# Memory.net
KiCad netlist of a schematic drawn in Altium Designer
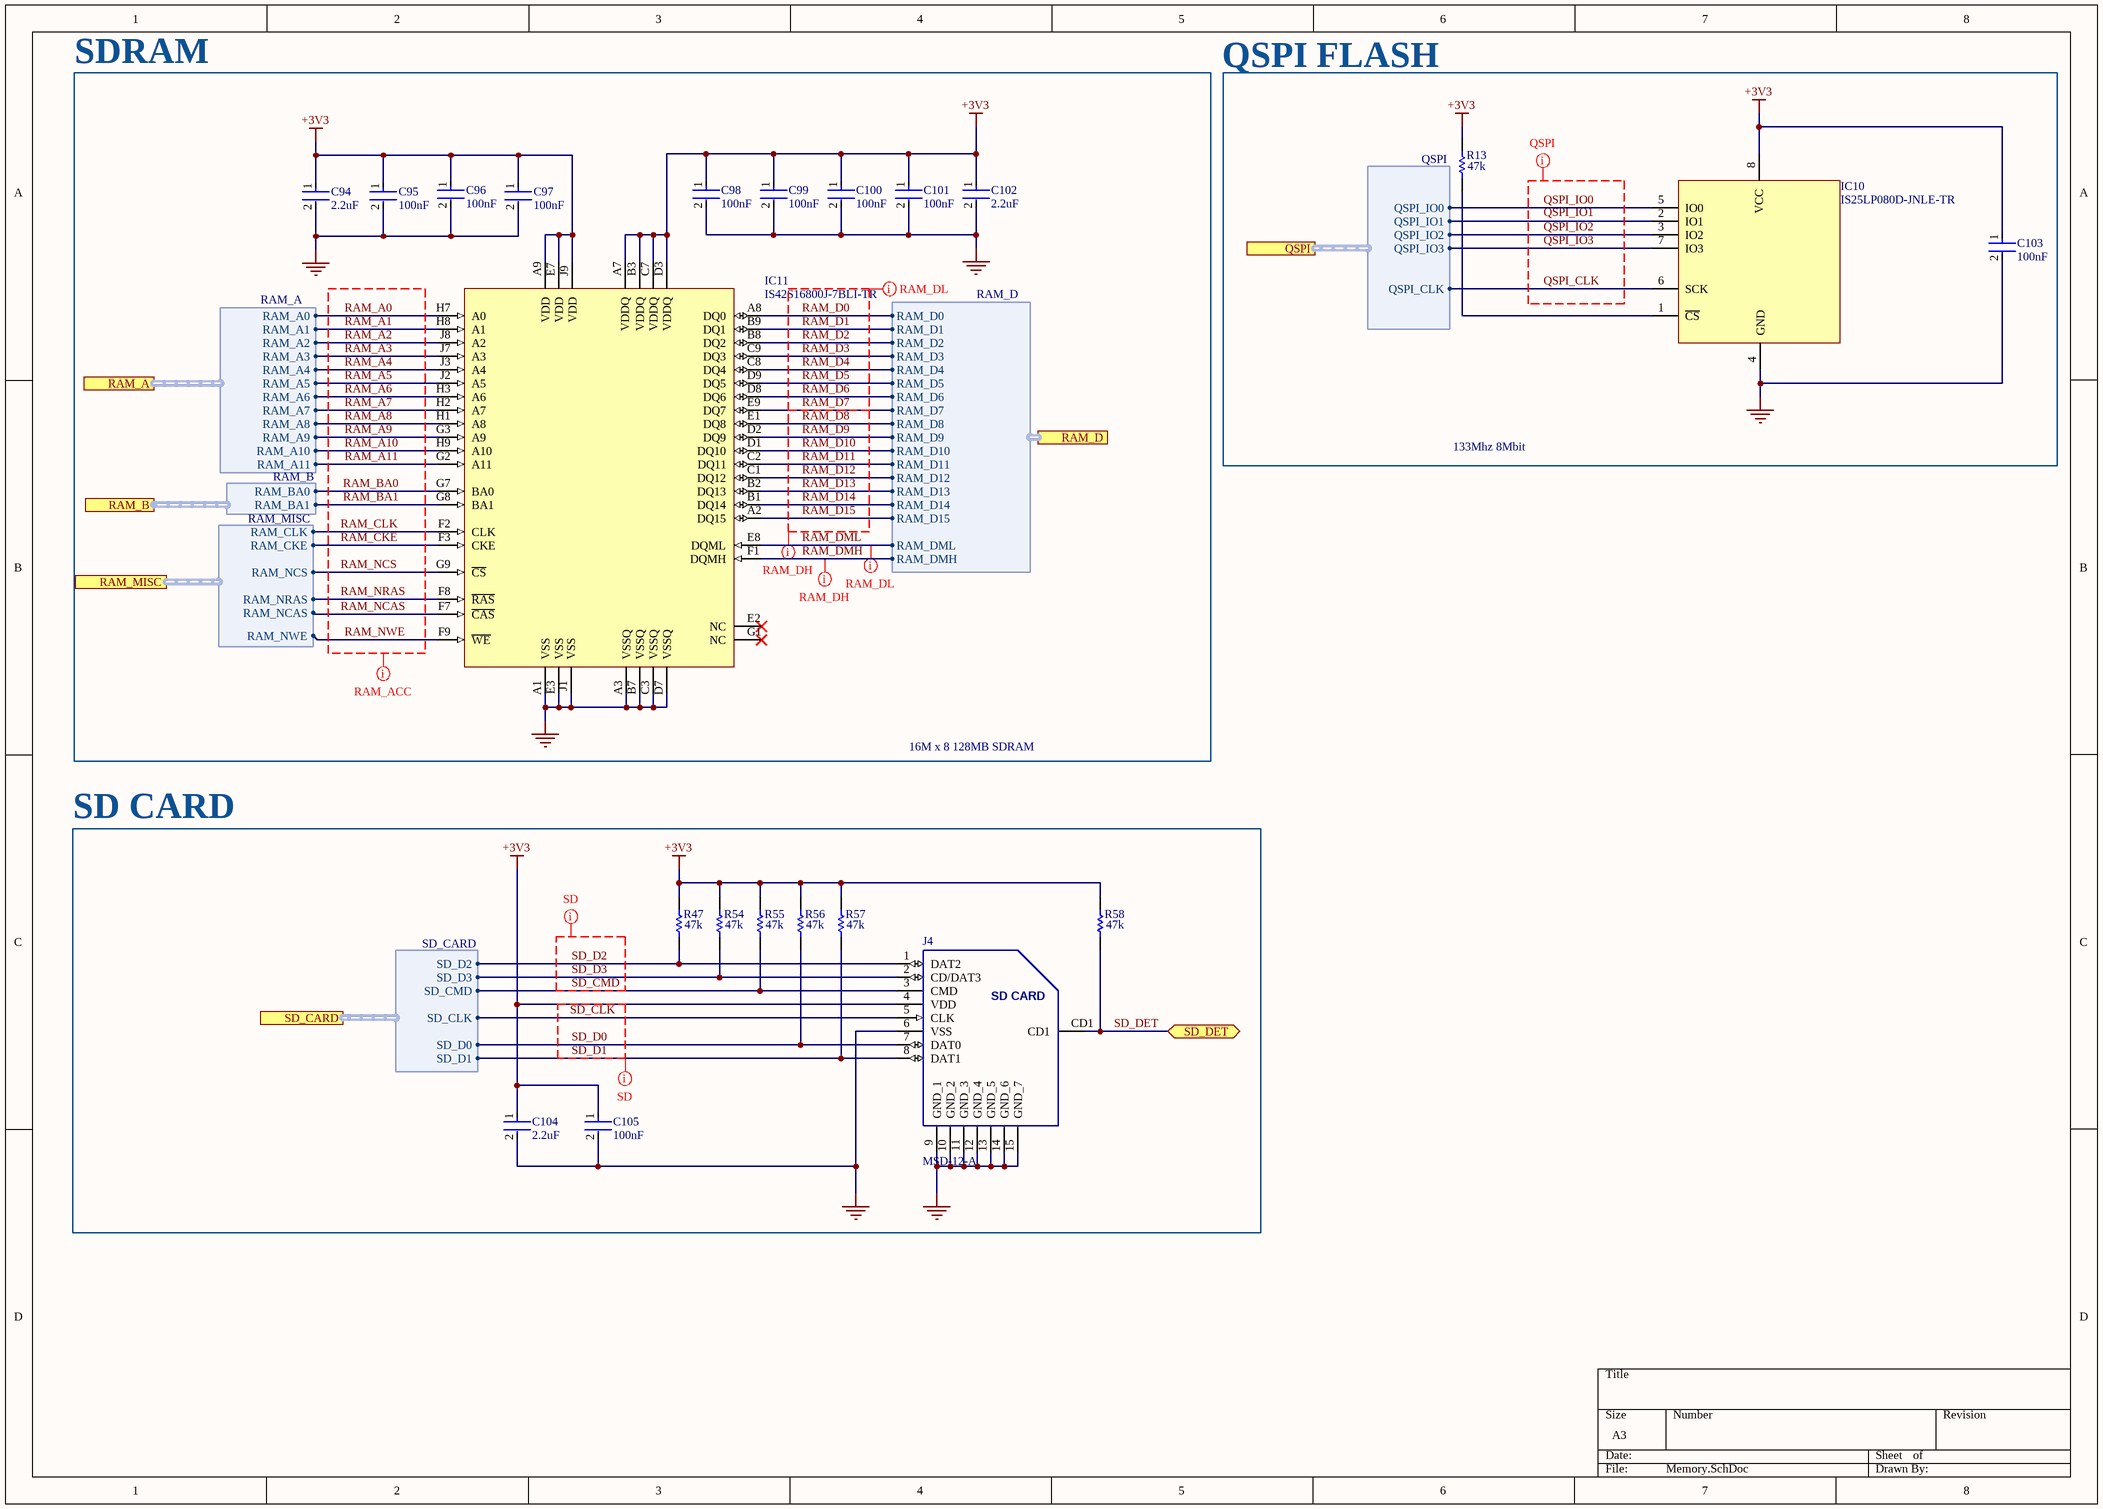
[diagram p0: Memory.SchDoc]

(export (version "E")
  (design (tool "Eeschema 10.0.6"))
  (components
    (comp (ref "C94")
      (value "GCM188C71A225KE02D")
      (footprint "FP-GCH188-0_1-e0_2_0_5-MFG")
      (description "GCM188C71A225KE02D Multilayer Ceramic Capacitor, 2.2 uF, 10 V, ± 10%, X7S, 0603 [1608 Metric]")
      (fields (field (name "CAPACITANCE") "2.2uF"))
      (libsource (lib "Altium Content Vault") (part "b4654b650e69147ec39a6b967a45e02"))
    )
    (comp (ref "C95")
      (value "GCM155R71H104ME02J")
      (footprint "FP-GCM155-0_05-IPC_A")
      (description "Ceramic Capacitor for Automotive 100nF ±20% 50VDC X7R 0402 Paper T/R")
      (fields (field (name "CAPACITANCE") "100nF"))
      (libsource (lib "Altium Content Vault") (part "02cd4be3c70576c341d710602a673aa"))
    )
    (comp (ref "C96")
      (value "GCM155R71H104ME02J")
      (footprint "FP-GCM155-0_05-IPC_A")
      (description "Ceramic Capacitor for Automotive 100nF ±20% 50VDC X7R 0402 Paper T/R")
      (fields (field (name "CAPACITANCE") "100nF"))
      (libsource (lib "Altium Content Vault") (part "02cd4be3c70576c341d710602a673aa"))
    )
    (comp (ref "C97")
      (value "GCM155R71H104ME02J")
      (footprint "FP-GCM155-0_05-IPC_A")
      (description "Ceramic Capacitor for Automotive 100nF ±20% 50VDC X7R 0402 Paper T/R")
      (fields (field (name "CAPACITANCE") "100nF"))
      (libsource (lib "Altium Content Vault") (part "02cd4be3c70576c341d710602a673aa"))
    )
    (comp (ref "C98")
      (value "GCM155R71H104ME02J")
      (footprint "FP-GCM155-0_05-IPC_A")
      (description "Ceramic Capacitor for Automotive 100nF ±20% 50VDC X7R 0402 Paper T/R")
      (fields (field (name "CAPACITANCE") "100nF"))
      (libsource (lib "Altium Content Vault") (part "02cd4be3c70576c341d710602a673aa"))
    )
    (comp (ref "C99")
      (value "GCM155R71H104ME02J")
      (footprint "FP-GCM155-0_05-IPC_A")
      (description "Ceramic Capacitor for Automotive 100nF ±20% 50VDC X7R 0402 Paper T/R")
      (fields (field (name "CAPACITANCE") "100nF"))
      (libsource (lib "Altium Content Vault") (part "02cd4be3c70576c341d710602a673aa"))
    )
    (comp (ref "C100")
      (value "GCM155R71H104ME02J")
      (footprint "FP-GCM155-0_05-IPC_A")
      (description "Ceramic Capacitor for Automotive 100nF ±20% 50VDC X7R 0402 Paper T/R")
      (fields (field (name "CAPACITANCE") "100nF"))
      (libsource (lib "Altium Content Vault") (part "02cd4be3c70576c341d710602a673aa"))
    )
    (comp (ref "C101")
      (value "GCM155R71H104ME02J")
      (footprint "FP-GCM155-0_05-IPC_A")
      (description "Ceramic Capacitor for Automotive 100nF ±20% 50VDC X7R 0402 Paper T/R")
      (fields (field (name "CAPACITANCE") "100nF"))
      (libsource (lib "Altium Content Vault") (part "02cd4be3c70576c341d710602a673aa"))
    )
    (comp (ref "C102")
      (value "GCM188C71A225KE02D")
      (footprint "FP-GCH188-0_1-e0_2_0_5-MFG")
      (description "GCM188C71A225KE02D Multilayer Ceramic Capacitor, 2.2 uF, 10 V, ± 10%, X7S, 0603 [1608 Metric]")
      (fields (field (name "CAPACITANCE") "2.2uF"))
      (libsource (lib "Altium Content Vault") (part "b4654b650e69147ec39a6b967a45e02"))
    )
    (comp (ref "C103")
      (value "GCM155R71H104ME02J")
      (footprint "FP-GCM155-0_05-IPC_A")
      (description "Ceramic Capacitor for Automotive 100nF ±20% 50VDC X7R 0402 Paper T/R")
      (fields (field (name "CAPACITANCE") "100nF"))
      (libsource (lib "Altium Content Vault") (part "02cd4be3c70576c341d710602a673aa"))
    )
    (comp (ref "C104")
      (value "GCM188C71A225KE02D")
      (footprint "FP-GCH188-0_1-e0_2_0_5-MFG")
      (description "GCM188C71A225KE02D Multilayer Ceramic Capacitor, 2.2 uF, 10 V, ± 10%, X7S, 0603 [1608 Metric]")
      (fields (field (name "CAPACITANCE") "2.2uF"))
      (libsource (lib "Altium Content Vault") (part "b4654b650e69147ec39a6b967a45e02"))
    )
    (comp (ref "C105")
      (value "GCM155R71H104ME02J")
      (footprint "FP-GCM155-0_05-IPC_A")
      (description "Ceramic Capacitor for Automotive 100nF ±20% 50VDC X7R 0402 Paper T/R")
      (fields (field (name "CAPACITANCE") "100nF"))
      (libsource (lib "Altium Content Vault") (part "02cd4be3c70576c341d710602a673aa"))
    )
    (comp (ref "IC10")
      (value "IS25LP080D-JNLE-TR")
      (footprint "SOIC127P600X175-8N")
      (description "Integrated Circuit")
      (fields (field (name "MOUSER PART NUMBER") "870-IS25LP080DJNLETR"))
      (libsource (lib "audio_dev_pcb") (part "IS25LP080D-JNLE-TR"))
    )
    (comp (ref "IC11")
      (value "IS42S16800J-7BLI-TR")
      (footprint "IS42S16800J-7BLI-TR")
      (description "Integrated Circuit")
      (libsource (lib "audio_dev_pcb") (part "IS42S16800J-7BLI-TR"))
    )
    (comp (ref "J4")
      (value "MSD-12-A")
      (footprint "MSD12A")
      (description "Connector")
      (fields (field (name "MOUSER PART NUMBER") "179-MSD-12-A"))
      (libsource (lib "audio_dev_pcb") (part "MSD-12-A"))
    )
    (comp (ref "R13")
      (value "RC0402JR-0747KL")
      (footprint "RESC1005X40X25LL05T10")
      (fields (field (name "MANUFACTURER") "Yageo / Phycomp") (field (name "RESISTANCE") "47k"))
      (libsource (lib "Altium Content Vault") (part "RES"))
    )
    (comp (ref "R47")
      (value "RC0402JR-0747KL")
      (footprint "RESC1005X40X25LL05T10")
      (fields (field (name "MANUFACTURER") "Yageo / Phycomp") (field (name "RESISTANCE") "47k"))
      (libsource (lib "Altium Content Vault") (part "RES"))
    )
    (comp (ref "R54")
      (value "RC0402JR-0747KL")
      (footprint "RESC1005X40X25LL05T10")
      (fields (field (name "MANUFACTURER") "Yageo / Phycomp") (field (name "RESISTANCE") "47k"))
      (libsource (lib "Altium Content Vault") (part "RES"))
    )
    (comp (ref "R55")
      (value "RC0402JR-0747KL")
      (footprint "RESC1005X40X25LL05T10")
      (fields (field (name "MANUFACTURER") "Yageo / Phycomp") (field (name "RESISTANCE") "47k"))
      (libsource (lib "Altium Content Vault") (part "RES"))
    )
    (comp (ref "R56")
      (value "RC0402JR-0747KL")
      (footprint "RESC1005X40X25LL05T10")
      (fields (field (name "MANUFACTURER") "Yageo / Phycomp") (field (name "RESISTANCE") "47k"))
      (libsource (lib "Altium Content Vault") (part "RES"))
    )
    (comp (ref "R57")
      (value "RC0402JR-0747KL")
      (footprint "RESC1005X40X25LL05T10")
      (fields (field (name "MANUFACTURER") "Yageo / Phycomp") (field (name "RESISTANCE") "47k"))
      (libsource (lib "Altium Content Vault") (part "RES"))
    )
    (comp (ref "R58")
      (value "RC0402JR-0747KL")
      (footprint "RESC1005X40X25LL05T10")
      (fields (field (name "MANUFACTURER") "Yageo / Phycomp") (field (name "RESISTANCE") "47k"))
      (libsource (lib "Altium Content Vault") (part "RES"))
    )
  )
  (nets
    (net (code "7") (name "+3V3") (class "Default")
      (node (ref "C100") (pin "1") (pinfunction "1_1") (pintype "passive"))
      (node (ref "C101") (pin "1") (pinfunction "1_1") (pintype "passive"))
      (node (ref "C102") (pin "1") (pinfunction "1_1") (pintype "passive"))
      (node (ref "C103") (pin "1") (pinfunction "1_1") (pintype "passive"))
      (node (ref "C104") (pin "1") (pinfunction "1_1") (pintype "passive"))
      (node (ref "C105") (pin "1") (pinfunction "1_1") (pintype "passive"))
      (node (ref "C94") (pin "1") (pinfunction "1_1") (pintype "passive"))
      (node (ref "C95") (pin "1") (pinfunction "1_1") (pintype "passive"))
      (node (ref "C96") (pin "1") (pinfunction "1_1") (pintype "passive"))
      (node (ref "C97") (pin "1") (pinfunction "1_1") (pintype "passive"))
      (node (ref "C98") (pin "1") (pinfunction "1_1") (pintype "passive"))
      (node (ref "C99") (pin "1") (pinfunction "1_1") (pintype "passive"))
      (node (ref "IC10") (pin "8") (pinfunction "VCC_8") (pintype "passive"))
      (node (ref "IC11") (pin "A7") (pinfunction "VDDQ_A7") (pintype "passive"))
      (node (ref "IC11") (pin "A9") (pinfunction "VDD_A9") (pintype "passive"))
      (node (ref "IC11") (pin "B3") (pinfunction "VDDQ_B3") (pintype "passive"))
      (node (ref "IC11") (pin "C7") (pinfunction "VDDQ_C7") (pintype "passive"))
      (node (ref "IC11") (pin "D3") (pinfunction "VDDQ_D3") (pintype "passive"))
      (node (ref "IC11") (pin "E7") (pinfunction "VDD_E7") (pintype "passive"))
      (node (ref "IC11") (pin "J9") (pinfunction "VDD_J9") (pintype "passive"))
      (node (ref "J4") (pin "4") (pinfunction "VDD_4") (pintype "passive"))
      (node (ref "R13") (pin "2") (pinfunction "2_2") (pintype "passive"))
      (node (ref "R47") (pin "2") (pinfunction "2_2") (pintype "passive"))
      (node (ref "R54") (pin "2") (pinfunction "2_2") (pintype "passive"))
      (node (ref "R55") (pin "2") (pinfunction "2_2") (pintype "passive"))
      (node (ref "R56") (pin "2") (pinfunction "2_2") (pintype "passive"))
      (node (ref "R57") (pin "2") (pinfunction "2_2") (pintype "passive"))
      (node (ref "R58") (pin "2") (pinfunction "2_2") (pintype "passive"))
    )
    (net (code "8") (name "/QSPI_CLK") (class "Default")
      (node (ref "IC10") (pin "6") (pinfunction "SCK_6") (pintype "passive"))
    )
    (net (code "9") (name "/QSPI_IO0") (class "Default")
      (node (ref "IC10") (pin "5") (pinfunction "IO0_5") (pintype "passive"))
    )
    (net (code "11") (name "/QSPI_IO2") (class "Default")
      (node (ref "IC10") (pin "3") (pinfunction "IO2_3") (pintype "passive"))
    )
    (net (code "12") (name "/QSPI_IO3") (class "Default")
      (node (ref "IC10") (pin "7") (pinfunction "IO3_7") (pintype "passive"))
    )
    (net (code "13") (name "/RAM_A0") (class "Default")
      (node (ref "IC11") (pin "H7") (pinfunction "A0_H7") (pintype "input"))
    )
    (net (code "14") (name "/RAM_A1") (class "Default")
      (node (ref "IC11") (pin "H8") (pinfunction "A1_H8") (pintype "input"))
    )
    (net (code "15") (name "/RAM_A2") (class "Default")
      (node (ref "IC11") (pin "J8") (pinfunction "A2_J8") (pintype "input"))
    )
    (net (code "16") (name "/RAM_A3") (class "Default")
      (node (ref "IC11") (pin "J7") (pinfunction "A3_J7") (pintype "input"))
    )
    (net (code "17") (name "/RAM_A4") (class "Default")
      (node (ref "IC11") (pin "J3") (pinfunction "A4_J3") (pintype "input"))
    )
    (net (code "18") (name "/RAM_A5") (class "Default")
      (node (ref "IC11") (pin "J2") (pinfunction "A5_J2") (pintype "input"))
    )
    (net (code "19") (name "/RAM_A6") (class "Default")
      (node (ref "IC11") (pin "H3") (pinfunction "A6_H3") (pintype "input"))
    )
    (net (code "20") (name "/RAM_A7") (class "Default")
      (node (ref "IC11") (pin "H2") (pinfunction "A7_H2") (pintype "input"))
    )
    (net (code "21") (name "/RAM_A8") (class "Default")
      (node (ref "IC11") (pin "H1") (pinfunction "A8_H1") (pintype "input"))
    )
    (net (code "22") (name "/RAM_A9") (class "Default")
      (node (ref "IC11") (pin "G3") (pinfunction "A9_G3") (pintype "input"))
    )
    (net (code "23") (name "/RAM_A10") (class "Default")
      (node (ref "IC11") (pin "H9") (pinfunction "A10_H9") (pintype "input"))
    )
    (net (code "24") (name "/RAM_A11") (class "Default")
      (node (ref "IC11") (pin "G2") (pinfunction "A11_G2") (pintype "input"))
    )
    (net (code "25") (name "/RAM_BA0") (class "Default")
      (node (ref "IC11") (pin "G7") (pinfunction "BA0_G7") (pintype "input"))
    )
    (net (code "26") (name "/RAM_BA1") (class "Default")
      (node (ref "IC11") (pin "G8") (pinfunction "BA1_G8") (pintype "input"))
    )
    (net (code "27") (name "/RAM_CKE") (class "Default")
      (node (ref "IC11") (pin "F3") (pinfunction "CKE_F3") (pintype "input"))
    )
    (net (code "28") (name "/RAM_CLK") (class "Default")
      (node (ref "IC11") (pin "F2") (pinfunction "CLK_F2") (pintype "input"))
    )
    (net (code "29") (name "/RAM_D0") (class "Default")
      (node (ref "IC11") (pin "A8") (pinfunction "DQ0_A8") (pintype "bidirectional"))
    )
    (net (code "30") (name "/RAM_D1") (class "Default")
      (node (ref "IC11") (pin "B9") (pinfunction "DQ1_B9") (pintype "bidirectional"))
    )
    (net (code "31") (name "/RAM_D2") (class "Default")
      (node (ref "IC11") (pin "B8") (pinfunction "DQ2_B8") (pintype "bidirectional"))
    )
    (net (code "32") (name "/RAM_D3") (class "Default")
      (node (ref "IC11") (pin "C9") (pinfunction "DQ3_C9") (pintype "bidirectional"))
    )
    (net (code "33") (name "/RAM_D4") (class "Default")
      (node (ref "IC11") (pin "C8") (pinfunction "DQ4_C8") (pintype "bidirectional"))
    )
    (net (code "34") (name "/RAM_D5") (class "Default")
      (node (ref "IC11") (pin "D9") (pinfunction "DQ5_D9") (pintype "bidirectional"))
    )
    (net (code "35") (name "/RAM_D6") (class "Default")
      (node (ref "IC11") (pin "D8") (pinfunction "DQ6_D8") (pintype "bidirectional"))
    )
    (net (code "36") (name "/RAM_D7") (class "Default")
      (node (ref "IC11") (pin "E9") (pinfunction "DQ7_E9") (pintype "bidirectional"))
    )
    (net (code "37") (name "/RAM_D8") (class "Default")
      (node (ref "IC11") (pin "E1") (pinfunction "DQ8_E1") (pintype "bidirectional"))
    )
    (net (code "38") (name "/RAM_D9") (class "Default")
      (node (ref "IC11") (pin "D2") (pinfunction "DQ9_D2") (pintype "bidirectional"))
    )
    (net (code "39") (name "/RAM_D10") (class "Default")
      (node (ref "IC11") (pin "D1") (pinfunction "DQ10_D1") (pintype "bidirectional"))
    )
    (net (code "40") (name "/RAM_D11") (class "Default")
      (node (ref "IC11") (pin "C2") (pinfunction "DQ11_C2") (pintype "bidirectional"))
    )
    (net (code "41") (name "/RAM_D12") (class "Default")
      (node (ref "IC11") (pin "C1") (pinfunction "DQ12_C1") (pintype "bidirectional"))
    )
    (net (code "42") (name "/RAM_D13") (class "Default")
      (node (ref "IC11") (pin "B2") (pinfunction "DQ13_B2") (pintype "bidirectional"))
    )
    (net (code "43") (name "/RAM_D14") (class "Default")
      (node (ref "IC11") (pin "B1") (pinfunction "DQ14_B1") (pintype "bidirectional"))
    )
    (net (code "44") (name "/RAM_D15") (class "Default")
      (node (ref "IC11") (pin "A2") (pinfunction "DQ15_A2") (pintype "bidirectional"))
    )
    (net (code "45") (name "/RAM_DMH") (class "Default")
      (node (ref "IC11") (pin "F1") (pinfunction "DQMH_F1") (pintype "input"))
    )
    (net (code "46") (name "/RAM_DML") (class "Default")
      (node (ref "IC11") (pin "E8") (pinfunction "DQML_E8") (pintype "input"))
    )
    (net (code "47") (name "/RAM_NCAS") (class "Default")
      (node (ref "IC11") (pin "F7") (pinfunction "~{CAS}_F7") (pintype "input"))
    )
    (net (code "48") (name "/RAM_NCS") (class "Default")
      (node (ref "IC11") (pin "G9") (pinfunction "~{CS}_G9") (pintype "input"))
    )
    (net (code "49") (name "/RAM_NRAS") (class "Default")
      (node (ref "IC11") (pin "F8") (pinfunction "~{RAS}_F8") (pintype "input"))
    )
    (net (code "50") (name "/RAM_NWE") (class "Default")
      (node (ref "IC11") (pin "F9") (pinfunction "~{WE}_F9") (pintype "input"))
    )
    (net (code "51") (name "/SD_CLK") (class "Default")
      (node (ref "J4") (pin "5") (pinfunction "CLK_5") (pintype "input"))
    )
    (net (code "52") (name "/SD_CMD") (class "Default")
      (node (ref "J4") (pin "3") (pinfunction "CMD_3") (pintype "passive"))
      (node (ref "R55") (pin "1") (pinfunction "1_1") (pintype "passive"))
    )
    (net (code "53") (name "/SD_D0") (class "Default")
      (node (ref "J4") (pin "7") (pinfunction "DAT0_7") (pintype "bidirectional"))
      (node (ref "R56") (pin "1") (pinfunction "1_1") (pintype "passive"))
    )
    (net (code "54") (name "/SD_D1") (class "Default")
      (node (ref "J4") (pin "8") (pinfunction "DAT1_8") (pintype "bidirectional"))
      (node (ref "R57") (pin "1") (pinfunction "1_1") (pintype "passive"))
    )
    (net (code "55") (name "/SD_D2") (class "Default")
      (node (ref "J4") (pin "1") (pinfunction "DAT2_1") (pintype "bidirectional"))
      (node (ref "R47") (pin "1") (pinfunction "1_1") (pintype "passive"))
    )
    (net (code "56") (name "/SD_D3") (class "Default")
      (node (ref "J4") (pin "2") (pinfunction "CD/DAT3_2") (pintype "bidirectional"))
      (node (ref "R54") (pin "1") (pinfunction "1_1") (pintype "passive"))
    )
    (net (code "57") (name "/SD_DET") (class "Default")
      (node (ref "J4") (pin "CD1") (pinfunction "CD1_CD1") (pintype "passive"))
      (node (ref "R58") (pin "1") (pinfunction "1_1") (pintype "passive"))
    )
    (net (code "64") (name "GND") (class "Default")
      (node (ref "C100") (pin "2") (pinfunction "2_2") (pintype "passive"))
      (node (ref "C101") (pin "2") (pinfunction "2_2") (pintype "passive"))
      (node (ref "C102") (pin "2") (pinfunction "2_2") (pintype "passive"))
      (node (ref "C103") (pin "2") (pinfunction "2_2") (pintype "passive"))
      (node (ref "C104") (pin "2") (pinfunction "2_2") (pintype "passive"))
      (node (ref "C105") (pin "2") (pinfunction "2_2") (pintype "passive"))
      (node (ref "C94") (pin "2") (pinfunction "2_2") (pintype "passive"))
      (node (ref "C95") (pin "2") (pinfunction "2_2") (pintype "passive"))
      (node (ref "C96") (pin "2") (pinfunction "2_2") (pintype "passive"))
      (node (ref "C97") (pin "2") (pinfunction "2_2") (pintype "passive"))
      (node (ref "C98") (pin "2") (pinfunction "2_2") (pintype "passive"))
      (node (ref "C99") (pin "2") (pinfunction "2_2") (pintype "passive"))
      (node (ref "IC10") (pin "4") (pinfunction "GND_4") (pintype "passive"))
      (node (ref "IC11") (pin "A1") (pinfunction "VSS_A1") (pintype "passive"))
      (node (ref "IC11") (pin "A3") (pinfunction "VSSQ_A3") (pintype "passive"))
      (node (ref "IC11") (pin "B7") (pinfunction "VSSQ_B7") (pintype "passive"))
      (node (ref "IC11") (pin "C3") (pinfunction "VSSQ_C3") (pintype "passive"))
      (node (ref "IC11") (pin "D7") (pinfunction "VSSQ_D7") (pintype "passive"))
      (node (ref "IC11") (pin "E3") (pinfunction "VSS_E3") (pintype "passive"))
      (node (ref "IC11") (pin "J1") (pinfunction "VSS_J1") (pintype "passive"))
      (node (ref "J4") (pin "10") (pinfunction "GND_2_10") (pintype "passive"))
      (node (ref "J4") (pin "11") (pinfunction "GND_3_11") (pintype "passive"))
      (node (ref "J4") (pin "12") (pinfunction "GND_4_12") (pintype "passive"))
      (node (ref "J4") (pin "13") (pinfunction "GND_5_13") (pintype "passive"))
      (node (ref "J4") (pin "14") (pinfunction "GND_6_14") (pintype "passive"))
      (node (ref "J4") (pin "15") (pinfunction "GND_7_15") (pintype "passive"))
      (node (ref "J4") (pin "6") (pinfunction "VSS_6") (pintype "passive"))
      (node (ref "J4") (pin "9") (pinfunction "GND_1_9") (pintype "passive"))
    )
    (net (code "65") (name "Net-(IC10-~{CS})") (class "Default")
      (node (ref "IC10") (pin "1") (pinfunction "~{CS}_1") (pintype "passive"))
      (node (ref "R13") (pin "1") (pinfunction "1_1") (pintype "passive"))
    )
    (net (code "66") (name "unconnected-(IC10-IO1-Pad2)") (class "Default")
      (node (ref "IC10") (pin "2") (pinfunction "IO1_2") (pintype "passive"))
    )
    (net (code "67") (name "unconnected-(IC11-NC-PadE2)") (class "Default")
      (node (ref "IC11") (pin "E2") (pinfunction "NC_E2") (pintype "passive+no_connect"))
    )
    (net (code "68") (name "unconnected-(IC11-NC-PadG1)") (class "Default")
      (node (ref "IC11") (pin "G1") (pinfunction "NC_G1") (pintype "passive+no_connect"))
    )
  )
)
